# IA-prop.net
KiCad netlist of a schematic drawn in EAGLE
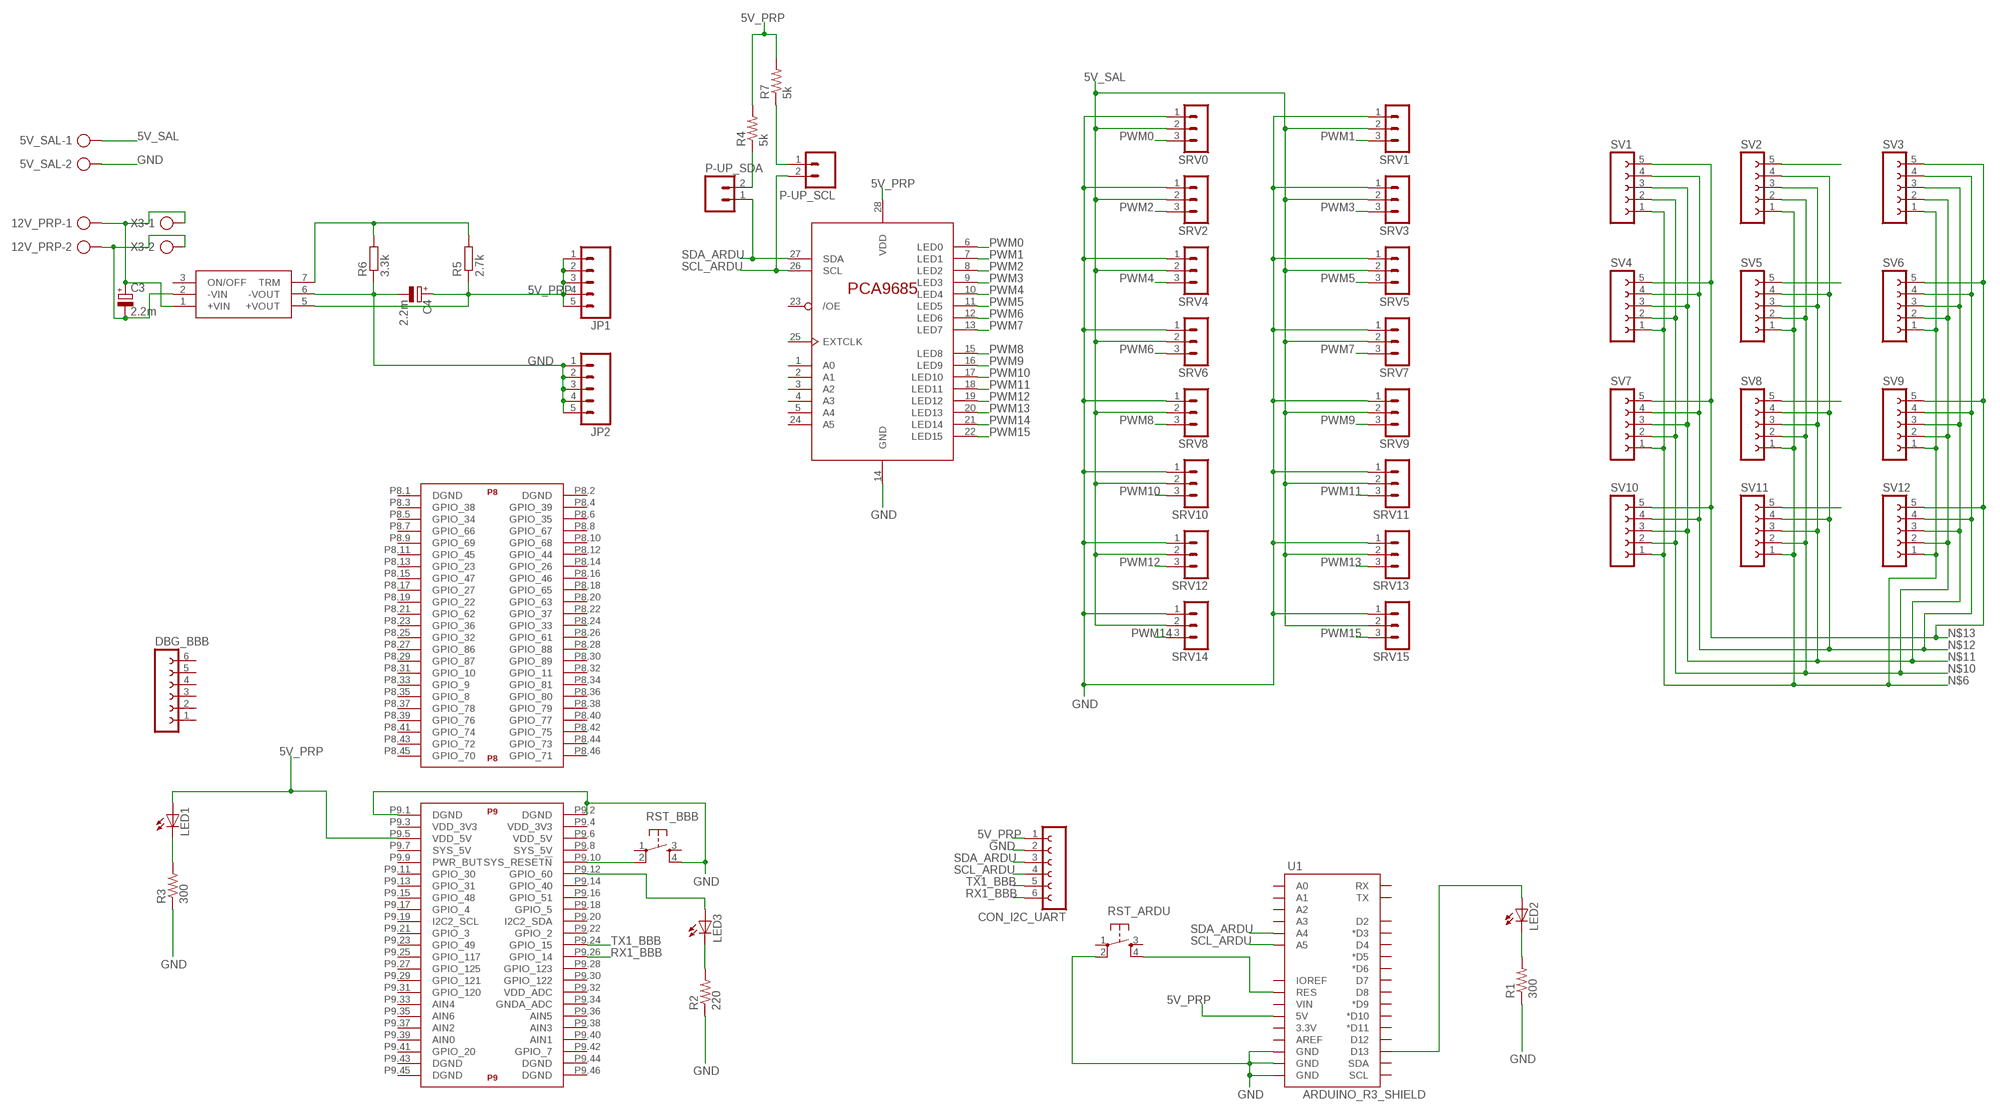
[diagram p0: schematic, sheet 1]

(export (version "E")
  (design (tool "Eeschema 10.0.6"))
  (components
    (comp (ref "5V_SAL")
      (value "AK300/2")
      (footprint "eagle-import:AK300_2")
      (fields (field (name "OC_FARNELL") "unknown") (field (name "OC_NEWARK") "unknown"))
      (libsource (lib "eagle-import") (part "AK300/2"))
    )
    (comp (ref "12V_PRP")
      (value "AK300/2")
      (footprint "eagle-import:AK300_2")
      (libsource (lib "eagle-import") (part "AK300/2"))
    )
    (comp (ref "C3")
      (value "2.2m")
      (footprint "eagle-import:E5-13")
      (libsource (lib "eagle-import") (part "CPOL-EUE5-13"))
    )
    (comp (ref "C4")
      (value "2.2m")
      (footprint "eagle-import:E5-13")
      (libsource (lib "eagle-import") (part "CPOL-EUE5-13"))
    )
    (comp (ref "CON_I2C_UART")
      (value "FE06-1")
      (footprint "eagle-import:FE06")
      (fields (field (name "OC_FARNELL") "unknown") (field (name "OC_NEWARK") "unknown"))
      (libsource (lib "eagle-import") (part "FE06-1"))
    )
    (comp (ref "DBG_BBB")
      (value "FE06-1")
      (footprint "eagle-import:FE06")
      (libsource (lib "eagle-import") (part "FE06-1"))
    )
    (comp (ref "JP1")
      (value "M05PTH")
      (footprint "eagle-import:1X05")
      (libsource (lib "eagle-import") (part "M05PTH"))
    )
    (comp (ref "JP2")
      (value "M05PTH")
      (footprint "eagle-import:1X05")
      (libsource (lib "eagle-import") (part "M05PTH"))
    )
    (comp (ref "LED1")
      (value "LED3MM")
      (footprint "eagle-import:LED3MM")
      (libsource (lib "eagle-import") (part "LED3MM"))
    )
    (comp (ref "LED2")
      (value "LED3MM")
      (footprint "eagle-import:LED3MM")
      (libsource (lib "eagle-import") (part "LED3MM"))
    )
    (comp (ref "LED3")
      (value "LED3MM")
      (footprint "eagle-import:LED3MM")
      (libsource (lib "eagle-import") (part "LED3MM"))
    )
    (comp (ref "P-UP_SCL")
      (value "M02PTH")
      (footprint "eagle-import:1X02")
      (libsource (lib "eagle-import") (part "M02PTH"))
    )
    (comp (ref "P-UP_SDA")
      (value "M02PTH")
      (footprint "eagle-import:1X02")
      (libsource (lib "eagle-import") (part "M02PTH"))
    )
    (comp (ref "R1")
      (value "300")
      (footprint "eagle-import:AXIAL-0.3")
      (libsource (lib "eagle-import") (part "RESISTORAXIAL-0.3"))
    )
    (comp (ref "R2")
      (value "220")
      (footprint "eagle-import:AXIAL-0.3")
      (libsource (lib "eagle-import") (part "RESISTORAXIAL-0.3"))
    )
    (comp (ref "R3")
      (value "300")
      (footprint "eagle-import:AXIAL-0.3")
      (libsource (lib "eagle-import") (part "RESISTORAXIAL-0.3"))
    )
    (comp (ref "R4")
      (value "5k")
      (footprint "eagle-import:AXIAL-0.3")
      (libsource (lib "eagle-import") (part "RESISTORAXIAL-0.3"))
    )
    (comp (ref "R5")
      (value "2.7k")
      (footprint "eagle-import:0207_7")
      (libsource (lib "eagle-import") (part "R-EU_0207/7"))
    )
    (comp (ref "R6")
      (value "3.3k")
      (footprint "eagle-import:0207_7")
      (libsource (lib "eagle-import") (part "R-EU_0207/7"))
    )
    (comp (ref "R7")
      (value "5k")
      (footprint "eagle-import:AXIAL-0.3")
      (libsource (lib "eagle-import") (part "RESISTORAXIAL-0.3"))
    )
    (comp (ref "RST_ARDU")
      (value "TAC_SWITCHPTH")
      (footprint "eagle-import:TACTILE-PTH")
      (libsource (lib "eagle-import") (part "TAC_SWITCHPTH"))
    )
    (comp (ref "RST_BBB")
      (value "TAC_SWITCHPTH")
      (footprint "eagle-import:TACTILE-PTH")
      (libsource (lib "eagle-import") (part "TAC_SWITCHPTH"))
    )
    (comp (ref "SRV0")
      (value "MA03-1")
      (footprint "eagle-import:MA03-1")
      (libsource (lib "eagle-import") (part "MA03-1"))
    )
    (comp (ref "SRV1")
      (value "MA03-1")
      (footprint "eagle-import:MA03-1")
      (libsource (lib "eagle-import") (part "MA03-1"))
    )
    (comp (ref "SRV2")
      (value "MA03-1")
      (footprint "eagle-import:MA03-1")
      (libsource (lib "eagle-import") (part "MA03-1"))
    )
    (comp (ref "SRV3")
      (value "MA03-1")
      (footprint "eagle-import:MA03-1")
      (libsource (lib "eagle-import") (part "MA03-1"))
    )
    (comp (ref "SRV4")
      (value "MA03-1")
      (footprint "eagle-import:MA03-1")
      (libsource (lib "eagle-import") (part "MA03-1"))
    )
    (comp (ref "SRV5")
      (value "MA03-1")
      (footprint "eagle-import:MA03-1")
      (libsource (lib "eagle-import") (part "MA03-1"))
    )
    (comp (ref "SRV6")
      (value "MA03-1")
      (footprint "eagle-import:MA03-1")
      (libsource (lib "eagle-import") (part "MA03-1"))
    )
    (comp (ref "SRV7")
      (value "MA03-1")
      (footprint "eagle-import:MA03-1")
      (libsource (lib "eagle-import") (part "MA03-1"))
    )
    (comp (ref "SRV8")
      (value "MA03-1")
      (footprint "eagle-import:MA03-1")
      (libsource (lib "eagle-import") (part "MA03-1"))
    )
    (comp (ref "SRV9")
      (value "MA03-1")
      (footprint "eagle-import:MA03-1")
      (libsource (lib "eagle-import") (part "MA03-1"))
    )
    (comp (ref "SRV10")
      (value "MA03-1")
      (footprint "eagle-import:MA03-1")
      (libsource (lib "eagle-import") (part "MA03-1"))
    )
    (comp (ref "SRV11")
      (value "MA03-1")
      (footprint "eagle-import:MA03-1")
      (libsource (lib "eagle-import") (part "MA03-1"))
    )
    (comp (ref "SRV12")
      (value "MA03-1")
      (footprint "eagle-import:MA03-1")
      (libsource (lib "eagle-import") (part "MA03-1"))
    )
    (comp (ref "SRV13")
      (value "MA03-1")
      (footprint "eagle-import:MA03-1")
      (libsource (lib "eagle-import") (part "MA03-1"))
    )
    (comp (ref "SRV14")
      (value "MA03-1")
      (footprint "eagle-import:MA03-1")
      (libsource (lib "eagle-import") (part "MA03-1"))
    )
    (comp (ref "SRV15")
      (value "MA03-1")
      (footprint "eagle-import:MA03-1")
      (libsource (lib "eagle-import") (part "MA03-1"))
    )
    (comp (ref "SV1")
      (value "FE05-1")
      (footprint "eagle-import:FE05-1")
      (libsource (lib "eagle-import") (part "FE05-1"))
    )
    (comp (ref "SV2")
      (value "FE05-1")
      (footprint "eagle-import:FE05-1")
      (libsource (lib "eagle-import") (part "FE05-1"))
    )
    (comp (ref "SV3")
      (value "FE05-1")
      (footprint "eagle-import:FE05-1")
      (libsource (lib "eagle-import") (part "FE05-1"))
    )
    (comp (ref "SV4")
      (value "FE05-1")
      (footprint "eagle-import:FE05-1")
      (libsource (lib "eagle-import") (part "FE05-1"))
    )
    (comp (ref "SV5")
      (value "FE05-1")
      (footprint "eagle-import:FE05-1")
      (libsource (lib "eagle-import") (part "FE05-1"))
    )
    (comp (ref "SV6")
      (value "FE05-1")
      (footprint "eagle-import:FE05-1")
      (libsource (lib "eagle-import") (part "FE05-1"))
    )
    (comp (ref "SV7")
      (value "FE05-1")
      (footprint "eagle-import:FE05-1")
      (libsource (lib "eagle-import") (part "FE05-1"))
    )
    (comp (ref "SV8")
      (value "FE05-1")
      (footprint "eagle-import:FE05-1")
      (libsource (lib "eagle-import") (part "FE05-1"))
    )
    (comp (ref "SV9")
      (value "FE05-1")
      (footprint "eagle-import:FE05-1")
      (libsource (lib "eagle-import") (part "FE05-1"))
    )
    (comp (ref "SV10")
      (value "FE05-1")
      (footprint "eagle-import:FE05-1")
      (libsource (lib "eagle-import") (part "FE05-1"))
    )
    (comp (ref "SV11")
      (value "FE05-1")
      (footprint "eagle-import:FE05-1")
      (libsource (lib "eagle-import") (part "FE05-1"))
    )
    (comp (ref "SV12")
      (value "FE05-1")
      (footprint "eagle-import:FE05-1")
      (libsource (lib "eagle-import") (part "FE05-1"))
    )
    (comp (ref "U$1")
      (value "PCA9685PW")
      (footprint "eagle-import:TSSOP28")
      (libsource (lib "eagle-import") (part "PCA9685PW"))
    )
    (comp (ref "U$2")
      (value "TEN25-1211TEN25-1211")
      (footprint "eagle-import:TEN25")
      (libsource (lib "eagle-import") (part "TEN25-1211TEN25-1211"))
    )
    (comp (ref "U$3")
      (value "BEAGLE_BONE_BLACK_CAPE")
      (footprint "eagle-import:BEAGLE_BONE_BLACK_CAPE")
      (libsource (lib "eagle-import") (part "BEAGLE_BONE_BLACK_CAPE"))
    )
    (comp (ref "U1")
      (value "ARDUINO_R3_SHIELD")
      (footprint "eagle-import:UNO_R3_SHIELD")
      (libsource (lib "eagle-import") (part "ARDUINO_R3_SHIELD"))
    )
    (comp (ref "X3")
      (value "AK300/2")
      (footprint "eagle-import:AK300_2")
      (libsource (lib "eagle-import") (part "AK300/2"))
    )
  )
  (nets
    (net (code "1") (name "/5V_PRP") (class "Default")
      (node (ref "C4") (pin "+") (pinfunction "+_+") (pintype "passive"))
      (node (ref "CON_I2C_UART") (pin "1") (pinfunction "1_1") (pintype "passive"))
      (node (ref "JP1") (pin "1") (pinfunction "1_1") (pintype "passive"))
      (node (ref "JP1") (pin "2") (pinfunction "2_2") (pintype "passive"))
      (node (ref "JP1") (pin "3") (pinfunction "3_3") (pintype "passive"))
      (node (ref "JP1") (pin "4") (pinfunction "4_4") (pintype "passive"))
      (node (ref "JP1") (pin "5") (pinfunction "5_5") (pintype "passive"))
      (node (ref "LED1") (pin "A") (pinfunction "A_A") (pintype "passive"))
      (node (ref "R4") (pin "P$2") (pinfunction "2_P$2") (pintype "passive"))
      (node (ref "R5") (pin "1") (pinfunction "1_1") (pintype "passive"))
      (node (ref "R7") (pin "P$2") (pinfunction "2_P$2") (pintype "passive"))
      (node (ref "U$1") (pin "28") (pinfunction "VDD_28") (pintype "power_in"))
      (node (ref "U$2") (pin "5") (pinfunction "+VOUT_5") (pintype "bidirectional"))
      (node (ref "U$3") (pin "P9.5") (pinfunction "VDD_5V_P9.5") (pintype "bidirectional"))
      (node (ref "U1") (pin "5V") (pinfunction "5V_5V") (pintype "bidirectional"))
    )
    (net (code "2") (name "/5V_SAL") (class "Default")
      (node (ref "5V_SAL") (pin "1") (pinfunction "KL_1") (pintype "passive"))
      (node (ref "SRV0") (pin "2") (pinfunction "2_2") (pintype "passive"))
      (node (ref "SRV1") (pin "2") (pinfunction "2_2") (pintype "passive"))
      (node (ref "SRV10") (pin "2") (pinfunction "2_2") (pintype "passive"))
      (node (ref "SRV11") (pin "2") (pinfunction "2_2") (pintype "passive"))
      (node (ref "SRV12") (pin "2") (pinfunction "2_2") (pintype "passive"))
      (node (ref "SRV13") (pin "2") (pinfunction "2_2") (pintype "passive"))
      (node (ref "SRV14") (pin "2") (pinfunction "2_2") (pintype "passive"))
      (node (ref "SRV15") (pin "2") (pinfunction "2_2") (pintype "passive"))
      (node (ref "SRV2") (pin "2") (pinfunction "2_2") (pintype "passive"))
      (node (ref "SRV3") (pin "2") (pinfunction "2_2") (pintype "passive"))
      (node (ref "SRV4") (pin "2") (pinfunction "2_2") (pintype "passive"))
      (node (ref "SRV5") (pin "2") (pinfunction "2_2") (pintype "passive"))
      (node (ref "SRV6") (pin "2") (pinfunction "2_2") (pintype "passive"))
      (node (ref "SRV7") (pin "2") (pinfunction "2_2") (pintype "passive"))
      (node (ref "SRV8") (pin "2") (pinfunction "2_2") (pintype "passive"))
      (node (ref "SRV9") (pin "2") (pinfunction "2_2") (pintype "passive"))
    )
    (net (code "3") (name "/GND") (class "Default")
      (node (ref "5V_SAL") (pin "2") (pinfunction "KL_2") (pintype "passive"))
      (node (ref "C4") (pin "-") (pinfunction "-_-") (pintype "passive"))
      (node (ref "CON_I2C_UART") (pin "2") (pinfunction "2_2") (pintype "passive"))
      (node (ref "JP2") (pin "1") (pinfunction "1_1") (pintype "passive"))
      (node (ref "JP2") (pin "2") (pinfunction "2_2") (pintype "passive"))
      (node (ref "JP2") (pin "3") (pinfunction "3_3") (pintype "passive"))
      (node (ref "JP2") (pin "4") (pinfunction "4_4") (pintype "passive"))
      (node (ref "JP2") (pin "5") (pinfunction "5_5") (pintype "passive"))
      (node (ref "R1") (pin "P$1") (pinfunction "1_P$1") (pintype "passive"))
      (node (ref "R2") (pin "P$1") (pinfunction "1_P$1") (pintype "passive"))
      (node (ref "R3") (pin "P$1") (pinfunction "1_P$1") (pintype "passive"))
      (node (ref "R6") (pin "1") (pinfunction "1_1") (pintype "passive"))
      (node (ref "RST_ARDU") (pin "2") (pinfunction "2_2") (pintype "passive"))
      (node (ref "RST_BBB") (pin "4") (pinfunction "4_4") (pintype "passive"))
      (node (ref "SRV0") (pin "1") (pinfunction "1_1") (pintype "passive"))
      (node (ref "SRV1") (pin "1") (pinfunction "1_1") (pintype "passive"))
      (node (ref "SRV10") (pin "1") (pinfunction "1_1") (pintype "passive"))
      (node (ref "SRV11") (pin "1") (pinfunction "1_1") (pintype "passive"))
      (node (ref "SRV12") (pin "1") (pinfunction "1_1") (pintype "passive"))
      (node (ref "SRV13") (pin "1") (pinfunction "1_1") (pintype "passive"))
      (node (ref "SRV14") (pin "1") (pinfunction "1_1") (pintype "passive"))
      (node (ref "SRV15") (pin "1") (pinfunction "1_1") (pintype "passive"))
      (node (ref "SRV2") (pin "1") (pinfunction "1_1") (pintype "passive"))
      (node (ref "SRV3") (pin "1") (pinfunction "1_1") (pintype "passive"))
      (node (ref "SRV4") (pin "1") (pinfunction "1_1") (pintype "passive"))
      (node (ref "SRV5") (pin "1") (pinfunction "1_1") (pintype "passive"))
      (node (ref "SRV6") (pin "1") (pinfunction "1_1") (pintype "passive"))
      (node (ref "SRV7") (pin "1") (pinfunction "1_1") (pintype "passive"))
      (node (ref "SRV8") (pin "1") (pinfunction "1_1") (pintype "passive"))
      (node (ref "SRV9") (pin "1") (pinfunction "1_1") (pintype "passive"))
      (node (ref "U$1") (pin "14") (pinfunction "GND_14") (pintype "power_in"))
      (node (ref "U$2") (pin "6") (pinfunction "-VOUT_6") (pintype "bidirectional"))
      (node (ref "U$3") (pin "P9.1") (pinfunction "DGND_P9.1") (pintype "bidirectional"))
      (node (ref "U$3") (pin "P9.2") (pinfunction "DGND_P9.2") (pintype "bidirectional"))
      (node (ref "U1") (pin "GND@0") (pinfunction "GND_GND@0") (pintype "bidirectional"))
      (node (ref "U1") (pin "GND@1") (pinfunction "GND_GND@1") (pintype "bidirectional"))
      (node (ref "U1") (pin "GND@2") (pinfunction "GND_GND@2") (pintype "bidirectional"))
    )
    (net (code "4") (name "/N$6") (class "Default")
      (node (ref "SV1") (pin "1") (pinfunction "1_1") (pintype "passive"))
      (node (ref "SV10") (pin "1") (pinfunction "1_1") (pintype "passive"))
      (node (ref "SV11") (pin "1") (pinfunction "1_1") (pintype "passive"))
      (node (ref "SV12") (pin "1") (pinfunction "1_1") (pintype "passive"))
      (node (ref "SV2") (pin "1") (pinfunction "1_1") (pintype "passive"))
      (node (ref "SV3") (pin "1") (pinfunction "1_1") (pintype "passive"))
      (node (ref "SV4") (pin "1") (pinfunction "1_1") (pintype "passive"))
      (node (ref "SV5") (pin "1") (pinfunction "1_1") (pintype "passive"))
      (node (ref "SV6") (pin "1") (pinfunction "1_1") (pintype "passive"))
      (node (ref "SV7") (pin "1") (pinfunction "1_1") (pintype "passive"))
      (node (ref "SV8") (pin "1") (pinfunction "1_1") (pintype "passive"))
      (node (ref "SV9") (pin "1") (pinfunction "1_1") (pintype "passive"))
    )
    (net (code "5") (name "/N$10") (class "Default")
      (node (ref "SV1") (pin "2") (pinfunction "2_2") (pintype "passive"))
      (node (ref "SV10") (pin "2") (pinfunction "2_2") (pintype "passive"))
      (node (ref "SV11") (pin "2") (pinfunction "2_2") (pintype "passive"))
      (node (ref "SV12") (pin "2") (pinfunction "2_2") (pintype "passive"))
      (node (ref "SV2") (pin "2") (pinfunction "2_2") (pintype "passive"))
      (node (ref "SV3") (pin "2") (pinfunction "2_2") (pintype "passive"))
      (node (ref "SV4") (pin "2") (pinfunction "2_2") (pintype "passive"))
      (node (ref "SV5") (pin "2") (pinfunction "2_2") (pintype "passive"))
      (node (ref "SV6") (pin "2") (pinfunction "2_2") (pintype "passive"))
      (node (ref "SV7") (pin "2") (pinfunction "2_2") (pintype "passive"))
      (node (ref "SV8") (pin "2") (pinfunction "2_2") (pintype "passive"))
      (node (ref "SV9") (pin "2") (pinfunction "2_2") (pintype "passive"))
    )
    (net (code "6") (name "/N$11") (class "Default")
      (node (ref "SV1") (pin "3") (pinfunction "3_3") (pintype "passive"))
      (node (ref "SV10") (pin "3") (pinfunction "3_3") (pintype "passive"))
      (node (ref "SV11") (pin "3") (pinfunction "3_3") (pintype "passive"))
      (node (ref "SV12") (pin "3") (pinfunction "3_3") (pintype "passive"))
      (node (ref "SV2") (pin "3") (pinfunction "3_3") (pintype "passive"))
      (node (ref "SV3") (pin "3") (pinfunction "3_3") (pintype "passive"))
      (node (ref "SV4") (pin "3") (pinfunction "3_3") (pintype "passive"))
      (node (ref "SV5") (pin "3") (pinfunction "3_3") (pintype "passive"))
      (node (ref "SV6") (pin "3") (pinfunction "3_3") (pintype "passive"))
      (node (ref "SV7") (pin "3") (pinfunction "3_3") (pintype "passive"))
      (node (ref "SV8") (pin "3") (pinfunction "3_3") (pintype "passive"))
      (node (ref "SV9") (pin "3") (pinfunction "3_3") (pintype "passive"))
    )
    (net (code "7") (name "/N$12") (class "Default")
      (node (ref "SV1") (pin "4") (pinfunction "4_4") (pintype "passive"))
      (node (ref "SV10") (pin "4") (pinfunction "4_4") (pintype "passive"))
      (node (ref "SV11") (pin "4") (pinfunction "4_4") (pintype "passive"))
      (node (ref "SV12") (pin "4") (pinfunction "4_4") (pintype "passive"))
      (node (ref "SV2") (pin "4") (pinfunction "4_4") (pintype "passive"))
      (node (ref "SV3") (pin "4") (pinfunction "4_4") (pintype "passive"))
      (node (ref "SV4") (pin "4") (pinfunction "4_4") (pintype "passive"))
      (node (ref "SV5") (pin "4") (pinfunction "4_4") (pintype "passive"))
      (node (ref "SV6") (pin "4") (pinfunction "4_4") (pintype "passive"))
      (node (ref "SV7") (pin "4") (pinfunction "4_4") (pintype "passive"))
      (node (ref "SV8") (pin "4") (pinfunction "4_4") (pintype "passive"))
      (node (ref "SV9") (pin "4") (pinfunction "4_4") (pintype "passive"))
    )
    (net (code "8") (name "/N$13") (class "Default")
      (node (ref "SV1") (pin "5") (pinfunction "5_5") (pintype "passive"))
      (node (ref "SV10") (pin "5") (pinfunction "5_5") (pintype "passive"))
      (node (ref "SV12") (pin "5") (pinfunction "5_5") (pintype "passive"))
      (node (ref "SV3") (pin "5") (pinfunction "5_5") (pintype "passive"))
      (node (ref "SV4") (pin "5") (pinfunction "5_5") (pintype "passive"))
      (node (ref "SV6") (pin "5") (pinfunction "5_5") (pintype "passive"))
      (node (ref "SV7") (pin "5") (pinfunction "5_5") (pintype "passive"))
      (node (ref "SV9") (pin "5") (pinfunction "5_5") (pintype "passive"))
    )
    (net (code "9") (name "/PWM0") (class "Default")
      (node (ref "SRV0") (pin "3") (pinfunction "3_3") (pintype "passive"))
      (node (ref "U$1") (pin "6") (pinfunction "LED0_6") (pintype "bidirectional"))
    )
    (net (code "10") (name "/PWM1") (class "Default")
      (node (ref "SRV1") (pin "3") (pinfunction "3_3") (pintype "passive"))
      (node (ref "U$1") (pin "7") (pinfunction "LED1_7") (pintype "bidirectional"))
    )
    (net (code "11") (name "/PWM2") (class "Default")
      (node (ref "SRV2") (pin "3") (pinfunction "3_3") (pintype "passive"))
      (node (ref "U$1") (pin "8") (pinfunction "LED2_8") (pintype "bidirectional"))
    )
    (net (code "12") (name "/PWM3") (class "Default")
      (node (ref "SRV3") (pin "3") (pinfunction "3_3") (pintype "passive"))
      (node (ref "U$1") (pin "9") (pinfunction "LED3_9") (pintype "bidirectional"))
    )
    (net (code "13") (name "/PWM4") (class "Default")
      (node (ref "SRV4") (pin "3") (pinfunction "3_3") (pintype "passive"))
      (node (ref "U$1") (pin "10") (pinfunction "LED4_10") (pintype "bidirectional"))
    )
    (net (code "14") (name "/PWM5") (class "Default")
      (node (ref "SRV5") (pin "3") (pinfunction "3_3") (pintype "passive"))
      (node (ref "U$1") (pin "11") (pinfunction "LED5_11") (pintype "bidirectional"))
    )
    (net (code "15") (name "/PWM6") (class "Default")
      (node (ref "SRV6") (pin "3") (pinfunction "3_3") (pintype "passive"))
      (node (ref "U$1") (pin "12") (pinfunction "LED6_12") (pintype "bidirectional"))
    )
    (net (code "16") (name "/PWM7") (class "Default")
      (node (ref "SRV7") (pin "3") (pinfunction "3_3") (pintype "passive"))
      (node (ref "U$1") (pin "13") (pinfunction "LED7_13") (pintype "bidirectional"))
    )
    (net (code "17") (name "/PWM8") (class "Default")
      (node (ref "SRV8") (pin "3") (pinfunction "3_3") (pintype "passive"))
      (node (ref "U$1") (pin "15") (pinfunction "LED8_15") (pintype "bidirectional"))
    )
    (net (code "18") (name "/PWM9") (class "Default")
      (node (ref "SRV9") (pin "3") (pinfunction "3_3") (pintype "passive"))
      (node (ref "U$1") (pin "16") (pinfunction "LED9_16") (pintype "bidirectional"))
    )
    (net (code "19") (name "/PWM10") (class "Default")
      (node (ref "SRV10") (pin "3") (pinfunction "3_3") (pintype "passive"))
      (node (ref "U$1") (pin "17") (pinfunction "LED10_17") (pintype "bidirectional"))
    )
    (net (code "20") (name "/PWM11") (class "Default")
      (node (ref "SRV11") (pin "3") (pinfunction "3_3") (pintype "passive"))
      (node (ref "U$1") (pin "18") (pinfunction "LED11_18") (pintype "bidirectional"))
    )
    (net (code "21") (name "/PWM12") (class "Default")
      (node (ref "SRV12") (pin "3") (pinfunction "3_3") (pintype "passive"))
      (node (ref "U$1") (pin "19") (pinfunction "LED12_19") (pintype "bidirectional"))
    )
    (net (code "22") (name "/PWM13") (class "Default")
      (node (ref "SRV13") (pin "3") (pinfunction "3_3") (pintype "passive"))
      (node (ref "U$1") (pin "20") (pinfunction "LED13_20") (pintype "bidirectional"))
    )
    (net (code "23") (name "/PWM14") (class "Default")
      (node (ref "SRV14") (pin "3") (pinfunction "3_3") (pintype "passive"))
      (node (ref "U$1") (pin "21") (pinfunction "LED14_21") (pintype "bidirectional"))
    )
    (net (code "24") (name "/PWM15") (class "Default")
      (node (ref "SRV15") (pin "3") (pinfunction "3_3") (pintype "passive"))
      (node (ref "U$1") (pin "22") (pinfunction "LED15_22") (pintype "bidirectional"))
    )
    (net (code "25") (name "/RX1_BBB") (class "Default")
      (node (ref "CON_I2C_UART") (pin "6") (pinfunction "6_6") (pintype "passive"))
      (node (ref "U$3") (pin "P9.26") (pinfunction "GPIO_14_P9.26") (pintype "bidirectional"))
    )
    (net (code "26") (name "/SCL_ARDU") (class "Default")
      (node (ref "CON_I2C_UART") (pin "4") (pinfunction "4_4") (pintype "passive"))
      (node (ref "P-UP_SCL") (pin "2") (pinfunction "2_2") (pintype "passive"))
      (node (ref "U$1") (pin "26") (pinfunction "SCL_26") (pintype "bidirectional"))
      (node (ref "U1") (pin "A5") (pinfunction "A5_A5") (pintype "bidirectional"))
    )
    (net (code "27") (name "/SDA_ARDU") (class "Default")
      (node (ref "CON_I2C_UART") (pin "3") (pinfunction "3_3") (pintype "passive"))
      (node (ref "P-UP_SDA") (pin "1") (pinfunction "1_1") (pintype "passive"))
      (node (ref "U$1") (pin "27") (pinfunction "SDA_27") (pintype "bidirectional"))
      (node (ref "U1") (pin "A4") (pinfunction "A4_A4") (pintype "bidirectional"))
    )
    (net (code "28") (name "/TX1_BBB") (class "Default")
      (node (ref "CON_I2C_UART") (pin "5") (pinfunction "5_5") (pintype "passive"))
      (node (ref "U$3") (pin "P9.24") (pinfunction "GPIO_15_P9.24") (pintype "bidirectional"))
    )
    (net (code "29") (name "Net-(12V_PRPA-KL)") (class "Default")
      (node (ref "12V_PRP") (pin "1") (pinfunction "KL_1") (pintype "passive"))
      (node (ref "C3") (pin "+") (pinfunction "+_+") (pintype "passive"))
      (node (ref "U$2") (pin "1") (pinfunction "+VIN_1") (pintype "bidirectional"))
      (node (ref "X3") (pin "1") (pinfunction "KL_1") (pintype "passive"))
    )
    (net (code "30") (name "Net-(12V_PRPB-KL)") (class "Default")
      (node (ref "12V_PRP") (pin "2") (pinfunction "KL_2") (pintype "passive"))
      (node (ref "C3") (pin "-") (pinfunction "-_-") (pintype "passive"))
      (node (ref "U$2") (pin "2") (pinfunction "-VIN_2") (pintype "bidirectional"))
      (node (ref "X3") (pin "2") (pinfunction "KL_2") (pintype "passive"))
    )
    (net (code "31") (name "Net-(LED1-C)") (class "Default")
      (node (ref "LED1") (pin "K") (pinfunction "C_K") (pintype "passive"))
      (node (ref "R3") (pin "P$2") (pinfunction "2_P$2") (pintype "passive"))
    )
    (net (code "32") (name "Net-(LED2-C)") (class "Default")
      (node (ref "LED2") (pin "K") (pinfunction "C_K") (pintype "passive"))
      (node (ref "R1") (pin "P$2") (pinfunction "2_P$2") (pintype "passive"))
    )
    (net (code "33") (name "Net-(LED2-PadA)") (class "Default")
      (node (ref "LED2") (pin "A") (pinfunction "A_A") (pintype "passive"))
      (node (ref "U1") (pin "D13") (pinfunction "D13_D13") (pintype "bidirectional"))
    )
    (net (code "34") (name "Net-(LED3-C)") (class "Default")
      (node (ref "LED3") (pin "K") (pinfunction "C_K") (pintype "passive"))
      (node (ref "R2") (pin "P$2") (pinfunction "2_P$2") (pintype "passive"))
    )
    (net (code "35") (name "Net-(R4-1)") (class "Default")
      (node (ref "P-UP_SDA") (pin "2") (pinfunction "2_2") (pintype "passive"))
      (node (ref "R4") (pin "P$1") (pinfunction "1_P$1") (pintype "passive"))
    )
    (net (code "36") (name "Net-(R7-1)") (class "Default")
      (node (ref "P-UP_SCL") (pin "1") (pinfunction "1_1") (pintype "passive"))
      (node (ref "R7") (pin "P$1") (pinfunction "1_P$1") (pintype "passive"))
    )
    (net (code "37") (name "Net-(RST_ARDU-Pad4)") (class "Default")
      (node (ref "RST_ARDU") (pin "4") (pinfunction "4_4") (pintype "passive"))
      (node (ref "U1") (pin "RES") (pinfunction "RES_RES") (pintype "bidirectional"))
    )
    (net (code "38") (name "Net-(U$2-TRM)") (class "Default")
      (node (ref "R5") (pin "2") (pinfunction "2_2") (pintype "passive"))
      (node (ref "R6") (pin "2") (pinfunction "2_2") (pintype "passive"))
      (node (ref "U$2") (pin "7") (pinfunction "TRM_7") (pintype "bidirectional"))
    )
    (net (code "39") (name "Net-(U$3B-GPIO_60)") (class "Default")
      (node (ref "LED3") (pin "A") (pinfunction "A_A") (pintype "passive"))
      (node (ref "U$3") (pin "P9.12") (pinfunction "GPIO_60_P9.12") (pintype "bidirectional"))
    )
    (net (code "40") (name "Net-(U$3B-SYS_RESET~{N})") (class "Default")
      (node (ref "RST_BBB") (pin "2") (pinfunction "2_2") (pintype "passive"))
      (node (ref "U$3") (pin "P9.10") (pinfunction "SYS_RESET~{N}_P9.10") (pintype "bidirectional"))
    )
    (net (code "41") (name "unconnected-(DBG_BBB-Pad1)") (class "Default")
      (node (ref "DBG_BBB") (pin "1") (pinfunction "1_1") (pintype "passive"))
    )
    (net (code "42") (name "unconnected-(DBG_BBB-Pad2)") (class "Default")
      (node (ref "DBG_BBB") (pin "2") (pinfunction "2_2") (pintype "passive"))
    )
    (net (code "43") (name "unconnected-(DBG_BBB-Pad3)") (class "Default")
      (node (ref "DBG_BBB") (pin "3") (pinfunction "3_3") (pintype "passive"))
    )
    (net (code "44") (name "unconnected-(DBG_BBB-Pad4)") (class "Default")
      (node (ref "DBG_BBB") (pin "4") (pinfunction "4_4") (pintype "passive"))
    )
    (net (code "45") (name "unconnected-(DBG_BBB-Pad5)") (class "Default")
      (node (ref "DBG_BBB") (pin "5") (pinfunction "5_5") (pintype "passive"))
    )
    (net (code "46") (name "unconnected-(DBG_BBB-Pad6)") (class "Default")
      (node (ref "DBG_BBB") (pin "6") (pinfunction "6_6") (pintype "passive"))
    )
    (net (code "47") (name "unconnected-(RST_ARDU-Pad1)") (class "Default")
      (node (ref "RST_ARDU") (pin "1") (pinfunction "1_1") (pintype "passive"))
    )
    (net (code "48") (name "unconnected-(RST_ARDU-Pad3)") (class "Default")
      (node (ref "RST_ARDU") (pin "3") (pinfunction "3_3") (pintype "passive"))
    )
    (net (code "49") (name "unconnected-(RST_BBB-Pad1)") (class "Default")
      (node (ref "RST_BBB") (pin "1") (pinfunction "1_1") (pintype "passive"))
    )
    (net (code "50") (name "unconnected-(RST_BBB-Pad3)") (class "Default")
      (node (ref "RST_BBB") (pin "3") (pinfunction "3_3") (pintype "passive"))
    )
    (net (code "51") (name "unconnected-(SV2-Pad5)") (class "Default")
      (node (ref "SV2") (pin "5") (pinfunction "5_5") (pintype "passive"))
    )
    (net (code "52") (name "unconnected-(SV5-Pad5)") (class "Default")
      (node (ref "SV5") (pin "5") (pinfunction "5_5") (pintype "passive"))
    )
    (net (code "53") (name "unconnected-(SV8-Pad5)") (class "Default")
      (node (ref "SV8") (pin "5") (pinfunction "5_5") (pintype "passive"))
    )
    (net (code "54") (name "unconnected-(SV11-Pad5)") (class "Default")
      (node (ref "SV11") (pin "5") (pinfunction "5_5") (pintype "passive"))
    )
    (net (code "55") (name "unconnected-(U$1-A0-Pad1)") (class "Default")
      (node (ref "U$1") (pin "1") (pinfunction "A0_1") (pintype "bidirectional"))
    )
    (net (code "56") (name "unconnected-(U$1-A1-Pad2)") (class "Default")
      (node (ref "U$1") (pin "2") (pinfunction "A1_2") (pintype "bidirectional"))
    )
    (net (code "57") (name "unconnected-(U$1-A2-Pad3)") (class "Default")
      (node (ref "U$1") (pin "3") (pinfunction "A2_3") (pintype "bidirectional"))
    )
    (net (code "58") (name "unconnected-(U$1-A3-Pad4)") (class "Default")
      (node (ref "U$1") (pin "4") (pinfunction "A3_4") (pintype "bidirectional"))
    )
    (net (code "59") (name "unconnected-(U$1-A4-Pad5)") (class "Default")
      (node (ref "U$1") (pin "5") (pinfunction "A4_5") (pintype "bidirectional"))
    )
    (net (code "60") (name "unconnected-(U$1-A5-Pad24)") (class "Default")
      (node (ref "U$1") (pin "24") (pinfunction "A5_24") (pintype "bidirectional"))
    )
    (net (code "61") (name "unconnected-(U$1-EXTCLK-Pad25)") (class "Default")
      (node (ref "U$1") (pin "25") (pinfunction "EXTCLK_25") (pintype "input"))
    )
    (net (code "62") (name "unconnected-(U$1-{slash}OE-Pad23)") (class "Default")
      (node (ref "U$1") (pin "23") (pinfunction "/OE_23") (pintype "bidirectional"))
    )
    (net (code "63") (name "unconnected-(U$2-ON{slash}OFF-Pad3)") (class "Default")
      (node (ref "U$2") (pin "3") (pinfunction "ON/OFF_3") (pintype "bidirectional"))
    )
    (net (code "64") (name "unconnected-(U$3A-DGND-PadP8.1)") (class "Default")
      (node (ref "U$3") (pin "P8.1") (pinfunction "DGND_P8.1") (pintype "bidirectional"))
    )
    (net (code "65") (name "unconnected-(U$3A-DGND-PadP8.2)") (class "Default")
      (node (ref "U$3") (pin "P8.2") (pinfunction "DGND_P8.2") (pintype "bidirectional"))
    )
    (net (code "66") (name "unconnected-(U$3A-GPIO_8-PadP8.35)") (class "Default")
      (node (ref "U$3") (pin "P8.35") (pinfunction "GPIO_8_P8.35") (pintype "bidirectional"))
    )
    (net (code "67") (name "unconnected-(U$3A-GPIO_9-PadP8.33)") (class "Default")
      (node (ref "U$3") (pin "P8.33") (pinfunction "GPIO_9_P8.33") (pintype "bidirectional"))
    )
    (net (code "68") (name "unconnected-(U$3A-GPIO_10-PadP8.31)") (class "Default")
      (node (ref "U$3") (pin "P8.31") (pinfunction "GPIO_10_P8.31") (pintype "bidirectional"))
    )
    (net (code "69") (name "unconnected-(U$3A-GPIO_11-PadP8.32)") (class "Default")
      (node (ref "U$3") (pin "P8.32") (pinfunction "GPIO_11_P8.32") (pintype "bidirectional"))
    )
    (net (code "70") (name "unconnected-(U$3A-GPIO_22-PadP8.19)") (class "Default")
      (node (ref "U$3") (pin "P8.19") (pinfunction "GPIO_22_P8.19") (pintype "bidirectional"))
    )
    (net (code "71") (name "unconnected-(U$3A-GPIO_23-PadP8.13)") (class "Default")
      (node (ref "U$3") (pin "P8.13") (pinfunction "GPIO_23_P8.13") (pintype "bidirectional"))
    )
    (net (code "72") (name "unconnected-(U$3A-GPIO_26-PadP8.14)") (class "Default")
      (node (ref "U$3") (pin "P8.14") (pinfunction "GPIO_26_P8.14") (pintype "bidirectional"))
    )
    (net (code "73") (name "unconnected-(U$3A-GPIO_27-PadP8.17)") (class "Default")
      (node (ref "U$3") (pin "P8.17") (pinfunction "GPIO_27_P8.17") (pintype "bidirectional"))
    )
    (net (code "74") (name "unconnected-(U$3A-GPIO_32-PadP8.25)") (class "Default")
      (node (ref "U$3") (pin "P8.25") (pinfunction "GPIO_32_P8.25") (pintype "bidirectional"))
    )
    (net (code "75") (name "unconnected-(U$3A-GPIO_33-PadP8.24)") (class "Default")
      (node (ref "U$3") (pin "P8.24") (pinfunction "GPIO_33_P8.24") (pintype "bidirectional"))
    )
    (net (code "76") (name "unconnected-(U$3A-GPIO_34-PadP8.5)") (class "Default")
      (node (ref "U$3") (pin "P8.5") (pinfunction "GPIO_34_P8.5") (pintype "bidirectional"))
    )
    (net (code "77") (name "unconnected-(U$3A-GPIO_35-PadP8.6)") (class "Default")
      (node (ref "U$3") (pin "P8.6") (pinfunction "GPIO_35_P8.6") (pintype "bidirectional"))
    )
    (net (code "78") (name "unconnected-(U$3A-GPIO_36-PadP8.23)") (class "Default")
      (node (ref "U$3") (pin "P8.23") (pinfunction "GPIO_36_P8.23") (pintype "bidirectional"))
    )
    (net (code "79") (name "unconnected-(U$3A-GPIO_37-PadP8.22)") (class "Default")
      (node (ref "U$3") (pin "P8.22") (pinfunction "GPIO_37_P8.22") (pintype "bidirectional"))
    )
    (net (code "80") (name "unconnected-(U$3A-GPIO_38-PadP8.3)") (class "Default")
      (node (ref "U$3") (pin "P8.3") (pinfunction "GPIO_38_P8.3") (pintype "bidirectional"))
    )
    (net (code "81") (name "unconnected-(U$3A-GPIO_39-PadP8.4)") (class "Default")
      (node (ref "U$3") (pin "P8.4") (pinfunction "GPIO_39_P8.4") (pintype "bidirectional"))
    )
    (net (code "82") (name "unconnected-(U$3A-GPIO_44-PadP8.12)") (class "Default")
      (node (ref "U$3") (pin "P8.12") (pinfunction "GPIO_44_P8.12") (pintype "bidirectional"))
    )
    (net (code "83") (name "unconnected-(U$3A-GPIO_45-PadP8.11)") (class "Default")
      (node (ref "U$3") (pin "P8.11") (pinfunction "GPIO_45_P8.11") (pintype "bidirectional"))
    )
    (net (code "84") (name "unconnected-(U$3A-GPIO_46-PadP8.16)") (class "Default")
      (node (ref "U$3") (pin "P8.16") (pinfunction "GPIO_46_P8.16") (pintype "bidirectional"))
    )
    (net (code "85") (name "unconnected-(U$3A-GPIO_47-PadP8.15)") (class "Default")
      (node (ref "U$3") (pin "P8.15") (pinfunction "GPIO_47_P8.15") (pintype "bidirectional"))
    )
    (net (code "86") (name "unconnected-(U$3A-GPIO_61-PadP8.26)") (class "Default")
      (node (ref "U$3") (pin "P8.26") (pinfunction "GPIO_61_P8.26") (pintype "bidirectional"))
    )
    (net (code "87") (name "unconnected-(U$3A-GPIO_62-PadP8.21)") (class "Default")
      (node (ref "U$3") (pin "P8.21") (pinfunction "GPIO_62_P8.21") (pintype "bidirectional"))
    )
    (net (code "88") (name "unconnected-(U$3A-GPIO_63-PadP8.20)") (class "Default")
      (node (ref "U$3") (pin "P8.20") (pinfunction "GPIO_63_P8.20") (pintype "bidirectional"))
    )
    (net (code "89") (name "unconnected-(U$3A-GPIO_65-PadP8.18)") (class "Default")
      (node (ref "U$3") (pin "P8.18") (pinfunction "GPIO_65_P8.18") (pintype "bidirectional"))
    )
    (net (code "90") (name "unconnected-(U$3A-GPIO_66-PadP8.7)") (class "Default")
      (node (ref "U$3") (pin "P8.7") (pinfunction "GPIO_66_P8.7") (pintype "bidirectional"))
    )
    (net (code "91") (name "unconnected-(U$3A-GPIO_67-PadP8.8)") (class "Default")
      (node (ref "U$3") (pin "P8.8") (pinfunction "GPIO_67_P8.8") (pintype "bidirectional"))
    )
    (net (code "92") (name "unconnected-(U$3A-GPIO_68-PadP8.10)") (class "Default")
      (node (ref "U$3") (pin "P8.10") (pinfunction "GPIO_68_P8.10") (pintype "bidirectional"))
    )
    (net (code "93") (name "unconnected-(U$3A-GPIO_69-PadP8.9)") (class "Default")
      (node (ref "U$3") (pin "P8.9") (pinfunction "GPIO_69_P8.9") (pintype "bidirectional"))
    )
    (net (code "94") (name "unconnected-(U$3A-GPIO_70-PadP8.45)") (class "Default")
      (node (ref "U$3") (pin "P8.45") (pinfunction "GPIO_70_P8.45") (pintype "bidirectional"))
    )
    (net (code "95") (name "unconnected-(U$3A-GPIO_71-PadP8.46)") (class "Default")
      (node (ref "U$3") (pin "P8.46") (pinfunction "GPIO_71_P8.46") (pintype "bidirectional"))
    )
    (net (code "96") (name "unconnected-(U$3A-GPIO_72-PadP8.43)") (class "Default")
      (node (ref "U$3") (pin "P8.43") (pinfunction "GPIO_72_P8.43") (pintype "bidirectional"))
    )
    (net (code "97") (name "unconnected-(U$3A-GPIO_73-PadP8.44)") (class "Default")
      (node (ref "U$3") (pin "P8.44") (pinfunction "GPIO_73_P8.44") (pintype "bidirectional"))
    )
    (net (code "98") (name "unconnected-(U$3A-GPIO_74-PadP8.41)") (class "Default")
      (node (ref "U$3") (pin "P8.41") (pinfunction "GPIO_74_P8.41") (pintype "bidirectional"))
    )
    (net (code "99") (name "unconnected-(U$3A-GPIO_75-PadP8.42)") (class "Default")
      (node (ref "U$3") (pin "P8.42") (pinfunction "GPIO_75_P8.42") (pintype "bidirectional"))
    )
    (net (code "100") (name "unconnected-(U$3A-GPIO_76-PadP8.39)") (class "Default")
      (node (ref "U$3") (pin "P8.39") (pinfunction "GPIO_76_P8.39") (pintype "bidirectional"))
    )
    (net (code "101") (name "unconnected-(U$3A-GPIO_77-PadP8.40)") (class "Default")
      (node (ref "U$3") (pin "P8.40") (pinfunction "GPIO_77_P8.40") (pintype "bidirectional"))
    )
    (net (code "102") (name "unconnected-(U$3A-GPIO_78-PadP8.37)") (class "Default")
      (node (ref "U$3") (pin "P8.37") (pinfunction "GPIO_78_P8.37") (pintype "bidirectional"))
    )
    (net (code "103") (name "unconnected-(U$3A-GPIO_79-PadP8.38)") (class "Default")
      (node (ref "U$3") (pin "P8.38") (pinfunction "GPIO_79_P8.38") (pintype "bidirectional"))
    )
    (net (code "104") (name "unconnected-(U$3A-GPIO_80-PadP8.36)") (class "Default")
      (node (ref "U$3") (pin "P8.36") (pinfunction "GPIO_80_P8.36") (pintype "bidirectional"))
    )
    (net (code "105") (name "unconnected-(U$3A-GPIO_81-PadP8.34)") (class "Default")
      (node (ref "U$3") (pin "P8.34") (pinfunction "GPIO_81_P8.34") (pintype "bidirectional"))
    )
    (net (code "106") (name "unconnected-(U$3A-GPIO_86-PadP8.27)") (class "Default")
      (node (ref "U$3") (pin "P8.27") (pinfunction "GPIO_86_P8.27") (pintype "bidirectional"))
    )
    (net (code "107") (name "unconnected-(U$3A-GPIO_87-PadP8.29)") (class "Default")
      (node (ref "U$3") (pin "P8.29") (pinfunction "GPIO_87_P8.29") (pintype "bidirectional"))
    )
    (net (code "108") (name "unconnected-(U$3A-GPIO_88-PadP8.28)") (class "Default")
      (node (ref "U$3") (pin "P8.28") (pinfunction "GPIO_88_P8.28") (pintype "bidirectional"))
    )
    (net (code "109") (name "unconnected-(U$3A-GPIO_89-PadP8.30)") (class "Default")
      (node (ref "U$3") (pin "P8.30") (pinfunction "GPIO_89_P8.30") (pintype "bidirectional"))
    )
    (net (code "110") (name "unconnected-(U$3B-AIN0-PadP9.39)") (class "Default")
      (node (ref "U$3") (pin "P9.39") (pinfunction "AIN0_P9.39") (pintype "bidirectional"))
    )
    (net (code "111") (name "unconnected-(U$3B-AIN1-PadP9.40)") (class "Default")
      (node (ref "U$3") (pin "P9.40") (pinfunction "AIN1_P9.40") (pintype "bidirectional"))
    )
    (net (code "112") (name "unconnected-(U$3B-AIN2-PadP9.37)") (class "Default")
      (node (ref "U$3") (pin "P9.37") (pinfunction "AIN2_P9.37") (pintype "bidirectional"))
    )
    (net (code "113") (name "unconnected-(U$3B-AIN3-PadP9.38)") (class "Default")
      (node (ref "U$3") (pin "P9.38") (pinfunction "AIN3_P9.38") (pintype "bidirectional"))
    )
    (net (code "114") (name "unconnected-(U$3B-AIN4-PadP9.33)") (class "Default")
      (node (ref "U$3") (pin "P9.33") (pinfunction "AIN4_P9.33") (pintype "bidirectional"))
    )
    (net (code "115") (name "unconnected-(U$3B-AIN5-PadP9.36)") (class "Default")
      (node (ref "U$3") (pin "P9.36") (pinfunction "AIN5_P9.36") (pintype "bidirectional"))
    )
    (net (code "116") (name "unconnected-(U$3B-AIN6-PadP9.35)") (class "Default")
      (node (ref "U$3") (pin "P9.35") (pinfunction "AIN6_P9.35") (pintype "bidirectional"))
    )
    (net (code "117") (name "unconnected-(U$3B-DGND-PadP9.43)") (class "Default")
      (node (ref "U$3") (pin "P9.43") (pinfunction "DGND_P9.43") (pintype "bidirectional"))
    )
    (net (code "118") (name "unconnected-(U$3B-DGND-PadP9.44)") (class "Default")
      (node (ref "U$3") (pin "P9.44") (pinfunction "DGND_P9.44") (pintype "bidirectional"))
    )
    (net (code "119") (name "unconnected-(U$3B-DGND-PadP9.45)") (class "Default")
      (node (ref "U$3") (pin "P9.45") (pinfunction "DGND_P9.45") (pintype "bidirectional"))
    )
    (net (code "120") (name "unconnected-(U$3B-DGND-PadP9.46)") (class "Default")
      (node (ref "U$3") (pin "P9.46") (pinfunction "DGND_P9.46") (pintype "bidirectional"))
    )
    (net (code "121") (name "unconnected-(U$3B-GNDA_ADC-PadP9.34)") (class "Default")
      (node (ref "U$3") (pin "P9.34") (pinfunction "GNDA_ADC_P9.34") (pintype "bidirectional"))
    )
    (net (code "122") (name "unconnected-(U$3B-GPIO_2-PadP9.22)") (class "Default")
      (node (ref "U$3") (pin "P9.22") (pinfunction "GPIO_2_P9.22") (pintype "bidirectional"))
    )
    (net (code "123") (name "unconnected-(U$3B-GPIO_3-PadP9.21)") (class "Default")
      (node (ref "U$3") (pin "P9.21") (pinfunction "GPIO_3_P9.21") (pintype "bidirectional"))
    )
    (net (code "124") (name "unconnected-(U$3B-GPIO_4-PadP9.17)") (class "Default")
      (node (ref "U$3") (pin "P9.17") (pinfunction "GPIO_4_P9.17") (pintype "bidirectional"))
    )
    (net (code "125") (name "unconnected-(U$3B-GPIO_5-PadP9.18)") (class "Default")
      (node (ref "U$3") (pin "P9.18") (pinfunction "GPIO_5_P9.18") (pintype "bidirectional"))
    )
    (net (code "126") (name "unconnected-(U$3B-GPIO_7-PadP9.42)") (class "Default")
      (node (ref "U$3") (pin "P9.42") (pinfunction "GPIO_7_P9.42") (pintype "bidirectional"))
    )
    (net (code "127") (name "unconnected-(U$3B-GPIO_20-PadP9.41)") (class "Default")
      (node (ref "U$3") (pin "P9.41") (pinfunction "GPIO_20_P9.41") (pintype "bidirectional"))
    )
    (net (code "128") (name "unconnected-(U$3B-GPIO_30-PadP9.11)") (class "Default")
      (node (ref "U$3") (pin "P9.11") (pinfunction "GPIO_30_P9.11") (pintype "bidirectional"))
    )
    (net (code "129") (name "unconnected-(U$3B-GPIO_31-PadP9.13)") (class "Default")
      (node (ref "U$3") (pin "P9.13") (pinfunction "GPIO_31_P9.13") (pintype "bidirectional"))
    )
    (net (code "130") (name "unconnected-(U$3B-GPIO_40-PadP9.14)") (class "Default")
      (node (ref "U$3") (pin "P9.14") (pinfunction "GPIO_40_P9.14") (pintype "bidirectional"))
    )
    (net (code "131") (name "unconnected-(U$3B-GPIO_48-PadP9.15)") (class "Default")
      (node (ref "U$3") (pin "P9.15") (pinfunction "GPIO_48_P9.15") (pintype "bidirectional"))
    )
    (net (code "132") (name "unconnected-(U$3B-GPIO_49-PadP9.23)") (class "Default")
      (node (ref "U$3") (pin "P9.23") (pinfunction "GPIO_49_P9.23") (pintype "bidirectional"))
    )
    (net (code "133") (name "unconnected-(U$3B-GPIO_51-PadP9.16)") (class "Default")
      (node (ref "U$3") (pin "P9.16") (pinfunction "GPIO_51_P9.16") (pintype "bidirectional"))
    )
    (net (code "134") (name "unconnected-(U$3B-GPIO_117-PadP9.25)") (class "Default")
      (node (ref "U$3") (pin "P9.25") (pinfunction "GPIO_117_P9.25") (pintype "bidirectional"))
    )
    (net (code "135") (name "unconnected-(U$3B-GPIO_120-PadP9.31)") (class "Default")
      (node (ref "U$3") (pin "P9.31") (pinfunction "GPIO_120_P9.31") (pintype "bidirectional"))
    )
    (net (code "136") (name "unconnected-(U$3B-GPIO_121-PadP9.29)") (class "Default")
      (node (ref "U$3") (pin "P9.29") (pinfunction "GPIO_121_P9.29") (pintype "bidirectional"))
    )
    (net (code "137") (name "unconnected-(U$3B-GPIO_122-PadP9.30)") (class "Default")
      (node (ref "U$3") (pin "P9.30") (pinfunction "GPIO_122_P9.30") (pintype "bidirectional"))
    )
    (net (code "138") (name "unconnected-(U$3B-GPIO_123-PadP9.28)") (class "Default")
      (node (ref "U$3") (pin "P9.28") (pinfunction "GPIO_123_P9.28") (pintype "bidirectional"))
    )
    (net (code "139") (name "unconnected-(U$3B-GPIO_125-PadP9.27)") (class "Default")
      (node (ref "U$3") (pin "P9.27") (pinfunction "GPIO_125_P9.27") (pintype "bidirectional"))
    )
    (net (code "140") (name "unconnected-(U$3B-I2C2_SCL-PadP9.19)") (class "Default")
      (node (ref "U$3") (pin "P9.19") (pinfunction "I2C2_SCL_P9.19") (pintype "bidirectional"))
    )
    (net (code "141") (name "unconnected-(U$3B-I2C2_SDA-PadP9.20)") (class "Default")
      (node (ref "U$3") (pin "P9.20") (pinfunction "I2C2_SDA_P9.20") (pintype "bidirectional"))
    )
    (net (code "142") (name "unconnected-(U$3B-PWR_BUT-PadP9.9)") (class "Default")
      (node (ref "U$3") (pin "P9.9") (pinfunction "PWR_BUT_P9.9") (pintype "bidirectional"))
    )
    (net (code "143") (name "unconnected-(U$3B-SYS_5V-PadP9.7)") (class "Default")
      (node (ref "U$3") (pin "P9.7") (pinfunction "SYS_5V_P9.7") (pintype "bidirectional"))
    )
    (net (code "144") (name "unconnected-(U$3B-SYS_5V-PadP9.8)") (class "Default")
      (node (ref "U$3") (pin "P9.8") (pinfunction "SYS_5V_P9.8") (pintype "bidirectional"))
    )
    (net (code "145") (name "unconnected-(U$3B-VDD_3V3-PadP9.3)") (class "Default")
      (node (ref "U$3") (pin "P9.3") (pinfunction "VDD_3V3_P9.3") (pintype "bidirectional"))
    )
    (net (code "146") (name "unconnected-(U$3B-VDD_3V3-PadP9.4)") (class "Default")
      (node (ref "U$3") (pin "P9.4") (pinfunction "VDD_3V3_P9.4") (pintype "bidirectional"))
    )
    (net (code "147") (name "unconnected-(U$3B-VDD_5V-PadP9.6)") (class "Default")
      (node (ref "U$3") (pin "P9.6") (pinfunction "VDD_5V_P9.6") (pintype "bidirectional"))
    )
    (net (code "148") (name "unconnected-(U$3B-VDD_ADC-PadP9.32)") (class "Default")
      (node (ref "U$3") (pin "P9.32") (pinfunction "VDD_ADC_P9.32") (pintype "bidirectional"))
    )
    (net (code "149") (name "unconnected-(U1-*D3-PadD3)") (class "Default")
      (node (ref "U1") (pin "D3") (pinfunction "*D3_D3") (pintype "bidirectional"))
    )
    (net (code "150") (name "unconnected-(U1-*D5-PadD5)") (class "Default")
      (node (ref "U1") (pin "D5") (pinfunction "*D5_D5") (pintype "bidirectional"))
    )
    (net (code "151") (name "unconnected-(U1-*D6-PadD6)") (class "Default")
      (node (ref "U1") (pin "D6") (pinfunction "*D6_D6") (pintype "bidirectional"))
    )
    (net (code "152") (name "unconnected-(U1-*D9-PadD9)") (class "Default")
      (node (ref "U1") (pin "D9") (pinfunction "*D9_D9") (pintype "bidirectional"))
    )
    (net (code "153") (name "unconnected-(U1-*D10-PadD10)") (class "Default")
      (node (ref "U1") (pin "D10") (pinfunction "*D10_D10") (pintype "bidirectional"))
    )
    (net (code "154") (name "unconnected-(U1-*D11-PadD11)") (class "Default")
      (node (ref "U1") (pin "D11") (pinfunction "*D11_D11") (pintype "bidirectional"))
    )
    (net (code "155") (name "unconnected-(U1-Pad3.3V)") (class "Default")
      (node (ref "U1") (pin "3.3V") (pinfunction "3.3V_3.3V") (pintype "bidirectional"))
    )
    (net (code "156") (name "unconnected-(U1-PadA0)") (class "Default")
      (node (ref "U1") (pin "A0") (pinfunction "A0_A0") (pintype "bidirectional"))
    )
    (net (code "157") (name "unconnected-(U1-PadA1)") (class "Default")
      (node (ref "U1") (pin "A1") (pinfunction "A1_A1") (pintype "bidirectional"))
    )
    (net (code "158") (name "unconnected-(U1-PadA2)") (class "Default")
      (node (ref "U1") (pin "A2") (pinfunction "A2_A2") (pintype "bidirectional"))
    )
    (net (code "159") (name "unconnected-(U1-PadA3)") (class "Default")
      (node (ref "U1") (pin "A3") (pinfunction "A3_A3") (pintype "bidirectional"))
    )
    (net (code "160") (name "unconnected-(U1-PadAREF)") (class "Default")
      (node (ref "U1") (pin "AREF") (pinfunction "AREF_AREF") (pintype "bidirectional"))
    )
    (net (code "161") (name "unconnected-(U1-PadD2)") (class "Default")
      (node (ref "U1") (pin "D2") (pinfunction "D2_D2") (pintype "bidirectional"))
    )
    (net (code "162") (name "unconnected-(U1-PadD4)") (class "Default")
      (node (ref "U1") (pin "D4") (pinfunction "D4_D4") (pintype "bidirectional"))
    )
    (net (code "163") (name "unconnected-(U1-PadD7)") (class "Default")
      (node (ref "U1") (pin "D7") (pinfunction "D7_D7") (pintype "bidirectional"))
    )
    (net (code "164") (name "unconnected-(U1-PadD8)") (class "Default")
      (node (ref "U1") (pin "D8") (pinfunction "D8_D8") (pintype "bidirectional"))
    )
    (net (code "165") (name "unconnected-(U1-PadD12)") (class "Default")
      (node (ref "U1") (pin "D12") (pinfunction "D12_D12") (pintype "bidirectional"))
    )
    (net (code "166") (name "unconnected-(U1-PadIOREF)") (class "Default")
      (node (ref "U1") (pin "IOREF") (pinfunction "IOREF_IOREF") (pintype "bidirectional"))
    )
    (net (code "167") (name "unconnected-(U1-PadRX)") (class "Default")
      (node (ref "U1") (pin "RX") (pinfunction "RX_RX") (pintype "bidirectional"))
    )
    (net (code "168") (name "unconnected-(U1-PadSCL)") (class "Default")
      (node (ref "U1") (pin "SCL") (pinfunction "SCL_SCL") (pintype "bidirectional"))
    )
    (net (code "169") (name "unconnected-(U1-PadSDA)") (class "Default")
      (node (ref "U1") (pin "SDA") (pinfunction "SDA_SDA") (pintype "bidirectional"))
    )
    (net (code "170") (name "unconnected-(U1-PadTX)") (class "Default")
      (node (ref "U1") (pin "TX") (pinfunction "TX_TX") (pintype "bidirectional"))
    )
    (net (code "171") (name "unconnected-(U1-PadVIN)") (class "Default")
      (node (ref "U1") (pin "VIN") (pinfunction "VIN_VIN") (pintype "bidirectional"))
    )
  )
)
